# 1-Schematic_CessnaCitationX_AP.net
KiCad netlist of a schematic drawn in EasyEDA
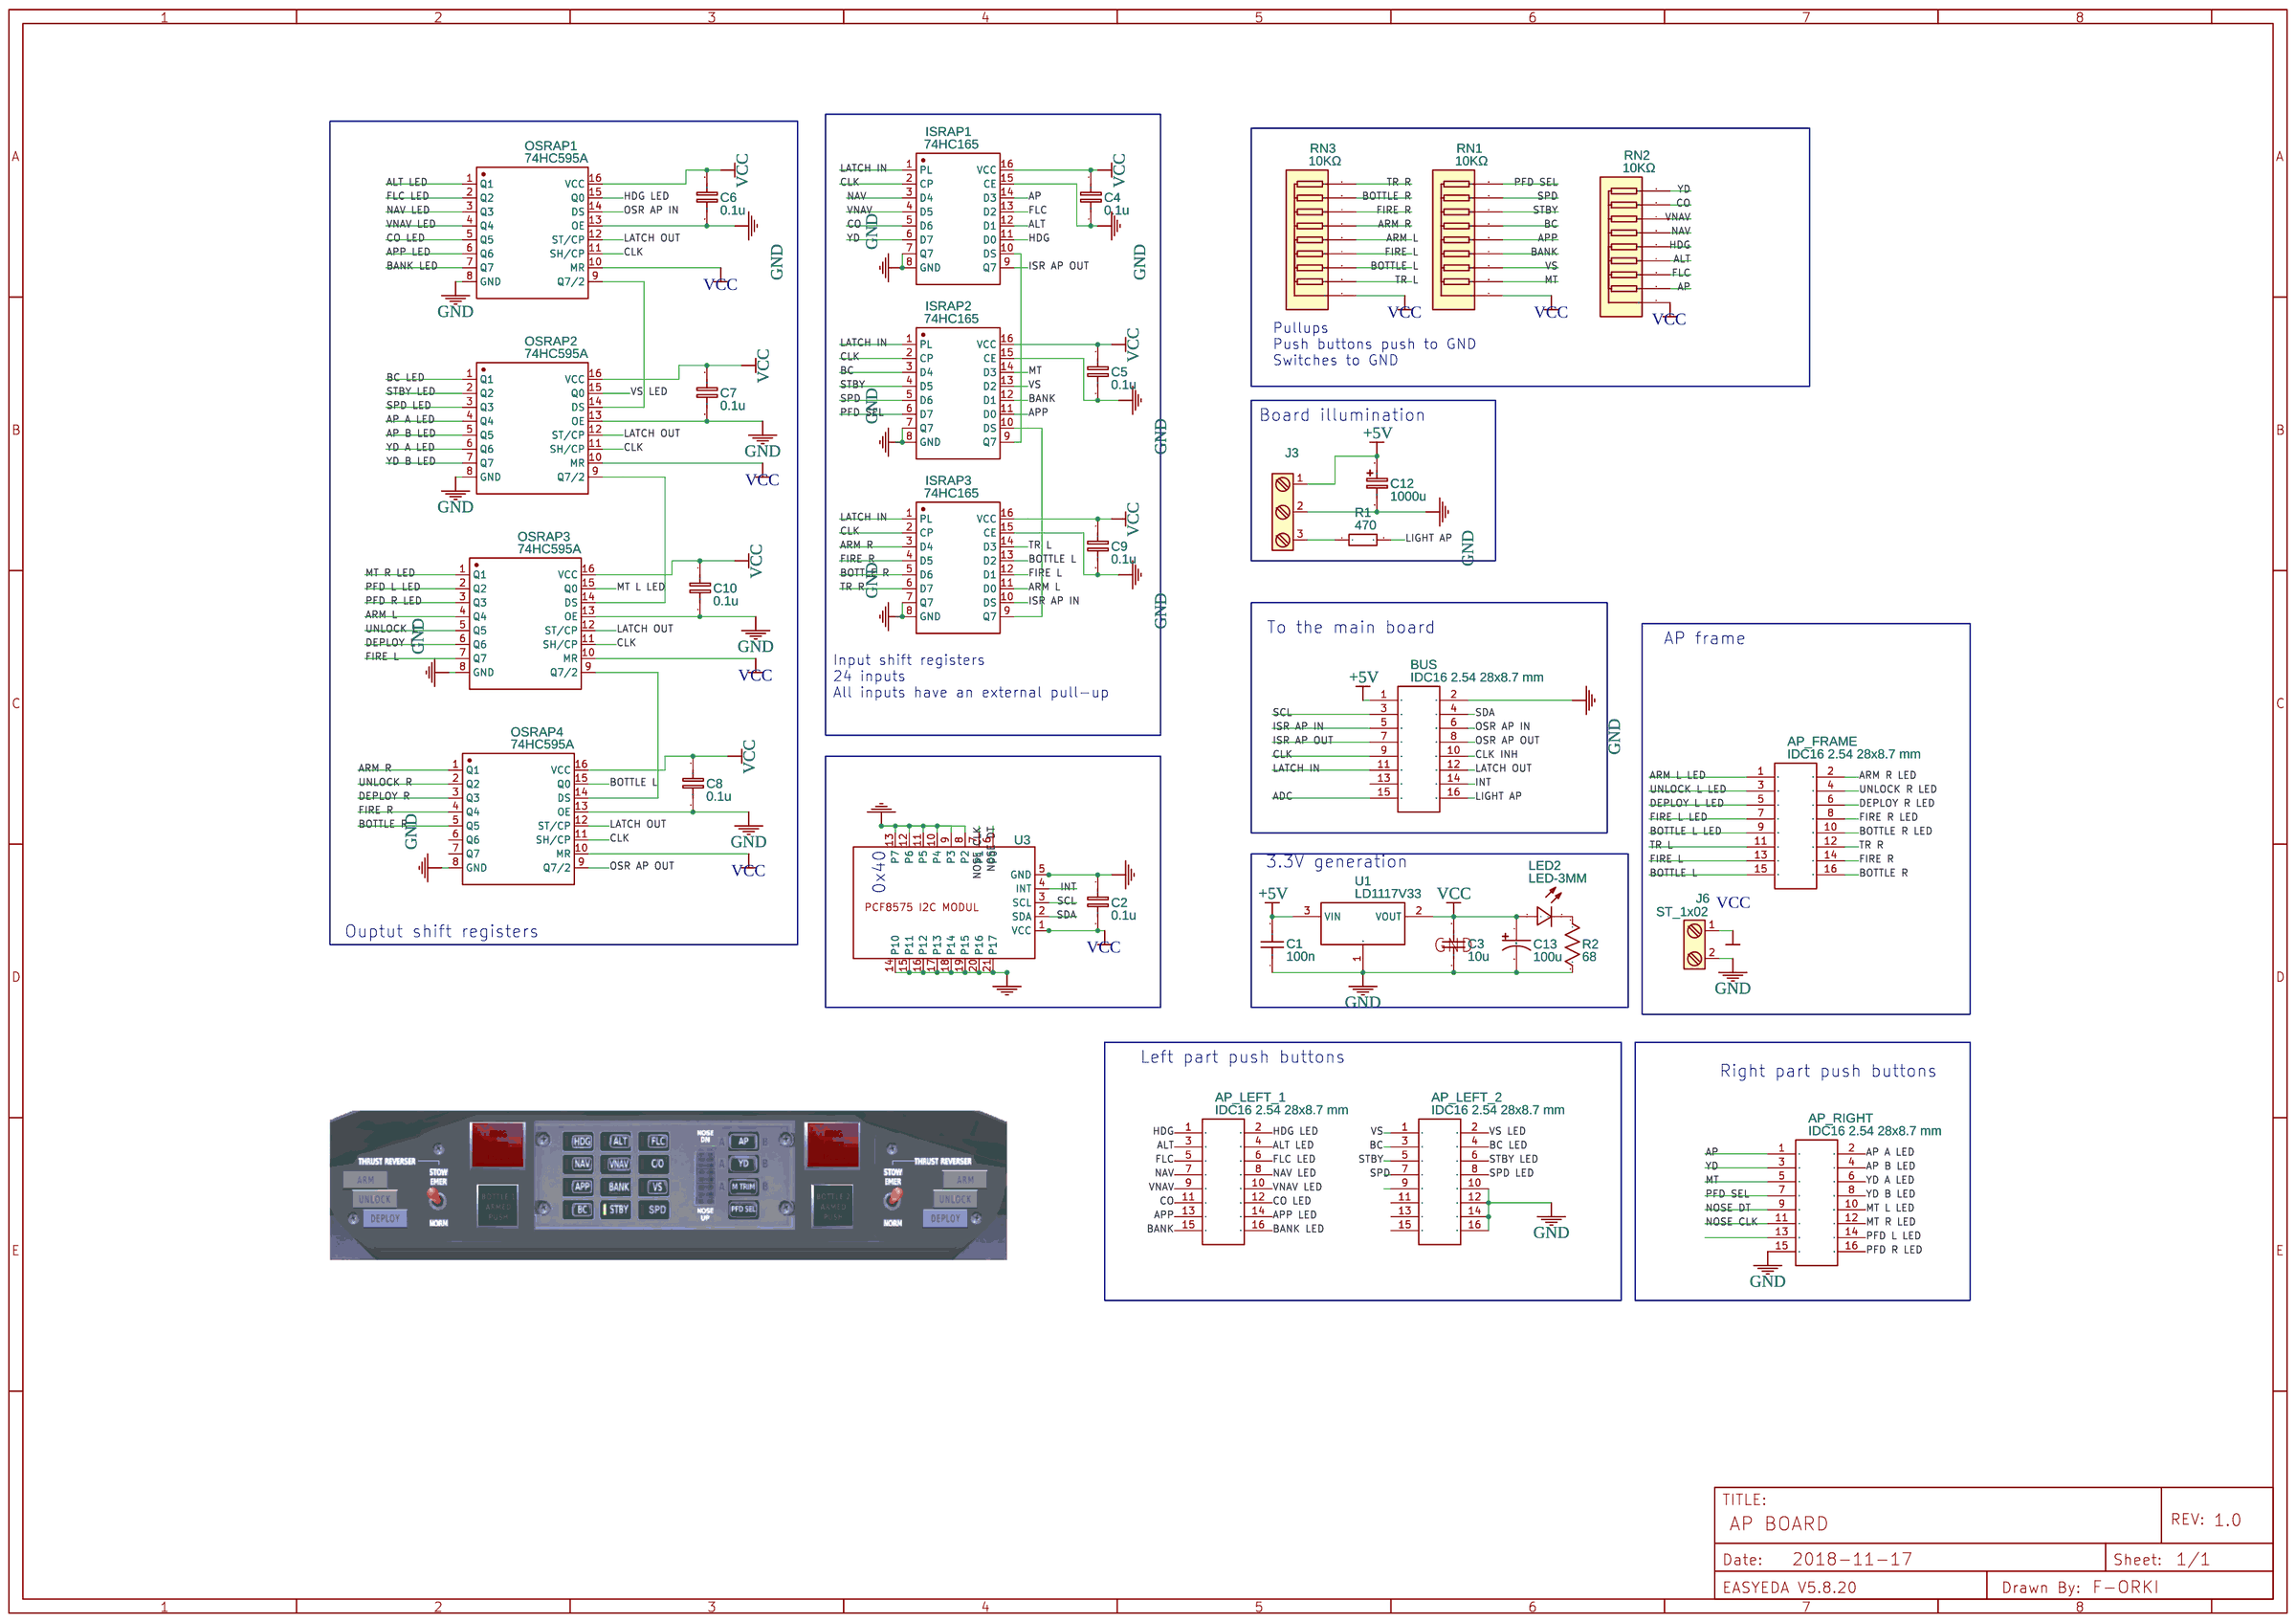
[diagram p0: schematic sheet]

(export (version "E")
  (design (tool "Eeschema 10.0.6"))
  (components
    (comp (ref "AP_FRAME")
      (value "IDC16 2.54 28x8.7 mm")
      (fields (field (name "BOM_Manufacturer Part") "?"))
      (libsource (lib "") (part "Unknown_1245_630"))
    )
    (comp (ref "AP_LEFT_1")
      (value "IDC16 2.54 28x8.7 mm")
      (fields (field (name "BOM_Manufacturer Part") "?"))
      (libsource (lib "") (part "Unknown_835_885"))
    )
    (comp (ref "AP_LEFT_2")
      (value "IDC16 2.54 28x8.7 mm")
      (fields (field (name "BOM_Manufacturer Part") "?"))
      (libsource (lib "") (part "Unknown_990_885"))
    )
    (comp (ref "AP_RIGHT")
      (value "IDC16 2.54 28x8.7 mm")
      (fields (field (name "BOM_Manufacturer Part") "?"))
      (libsource (lib "") (part "Unknown_1260_900"))
    )
    (comp (ref "BUS")
      (value "IDC16 2.54 28x8.7 mm")
      (fields (field (name "BOM_Manufacturer Part") "?"))
      (libsource (lib "") (part "Unknown_975_575"))
    )
    (comp (ref "C1")
      (value "100n")
      (fields (field (name "BOM_Manufacturer Part") "?"))
      (libsource (lib "") (part "Cap_RAD-0.1_US"))
    )
    (comp (ref "C2")
      (value "0.1u")
      (fields (field (name "BOM_Manufacturer Part") "?"))
      (libsource (lib "") (part "Cap_RAD-0.1_EU_1"))
    )
    (comp (ref "C3")
      (value "10u")
      (fields (field (name "BOM_Manufacturer Part") "?"))
      (libsource (lib "") (part "Cap_RAD-0.1_US"))
    )
    (comp (ref "C4")
      (value "0.1u")
      (fields (field (name "BOM_Manufacturer Part") "?"))
      (libsource (lib "") (part "Cap_RAD-0.1_EU"))
    )
    (comp (ref "C5")
      (value "0.1u")
      (fields (field (name "BOM_Manufacturer Part") "?"))
      (libsource (lib "") (part "Cap_RAD-0.1_EU"))
    )
    (comp (ref "C6")
      (value "0.1u")
      (fields (field (name "BOM_Manufacturer Part") "?"))
      (libsource (lib "") (part "Cap_RAD-0.1_EU_2"))
    )
    (comp (ref "C7")
      (value "0.1u")
      (fields (field (name "BOM_Manufacturer Part") "?"))
      (libsource (lib "") (part "Cap_RAD-0.1_EU_2"))
    )
    (comp (ref "C8")
      (value "0.1u")
      (fields (field (name "BOM_Manufacturer Part") "?"))
      (libsource (lib "") (part "Cap_RAD-0.1_EU_3"))
    )
    (comp (ref "C9")
      (value "0.1u")
      (fields (field (name "BOM_Manufacturer Part") "?"))
      (libsource (lib "") (part "Cap_RAD-0.1_EU"))
    )
    (comp (ref "C10")
      (value "0.1u")
      (fields (field (name "BOM_Manufacturer Part") "?"))
      (libsource (lib "") (part "Cap_RAD-0.1_EU_2"))
    )
    (comp (ref "C12")
      (value "1000u")
      (fields (field (name "BOM_Manufacturer Part") "?"))
      (libsource (lib "") (part "Cap_Electrolytic(TH)_D3.0XF1.5_EU"))
    )
    (comp (ref "C13")
      (value "100u")
      (fields (field (name "BOM_Manufacturer Part") "?"))
      (libsource (lib "") (part "Cap_Electrolytic(TH)_D3.0XF1.5_US"))
    )
    (comp (ref "ISRAP1")
      (value "74HC165")
      (fields
        (field (name "BOM_Manufacturer Part") "74HC165D,653")
        (field (name "BOM_Supplier Part") "C5613")
      )
      (libsource (lib "") (part "Unknown_680_105"))
    )
    (comp (ref "ISRAP2")
      (value "74HC165")
      (fields
        (field (name "BOM_Manufacturer Part") "74HC165D,653")
        (field (name "BOM_Supplier Part") "C5613")
      )
      (libsource (lib "") (part "Unknown_680_230"))
    )
    (comp (ref "ISRAP3")
      (value "74HC165")
      (fields
        (field (name "BOM_Manufacturer Part") "74HC165D,653")
        (field (name "BOM_Supplier Part") "C5613")
      )
      (libsource (lib "") (part "Unknown_680_355"))
    )
    (comp (ref "J3")
      (value "Screw_Terminal_1x03")
      (fields (field (name "BOM_Manufacturer Part") "?"))
      (libsource (lib "") (part "Unknown_920_360"))
    )
    (comp (ref "J6")
      (value "ST_1x02")
      (fields (field (name "BOM_Manufacturer Part") "?"))
      (libsource (lib "") (part "Unknown_1215_660"))
    )
    (comp (ref "LED2")
      (value "LED-3MM")
      (fields
        (field (name "BOM_Manufacturer Part") "204-10SURD/S530-A3")
        (field (name "BOM_Supplier Part") "C99772")
      )
      (libsource (lib "") (part "Unknown_1100_645"))
    )
    (comp (ref "OSRAP1")
      (value "74HC595A")
      (fields (field (name "BOM_Supplier Part") "C110383"))
      (libsource (lib "") (part "Unknown_375_115"))
    )
    (comp (ref "OSRAP2")
      (value "74HC595A")
      (fields (field (name "BOM_Supplier Part") "C110383"))
      (libsource (lib "") (part "Unknown_375_255"))
    )
    (comp (ref "OSRAP3")
      (value "74HC595A")
      (fields (field (name "BOM_Supplier Part") "C110383"))
      (libsource (lib "") (part "Unknown_370_395"))
    )
    (comp (ref "OSRAP4")
      (value "74HC595A")
      (fields (field (name "BOM_Supplier Part") "C110383"))
      (libsource (lib "") (part "Unknown_365_535"))
    )
    (comp (ref "R1")
      (value "470")
      (fields (field (name "BOM_Manufacturer Part") "?"))
      (libsource (lib "") (part "Res_AXIAL-0.3(1/8W)_EU"))
    )
    (comp (ref "R2")
      (value "68")
      (fields (field (name "BOM_Manufacturer Part") "?"))
      (libsource (lib "") (part "Res_AXIAL-0.3(1/8W)_US"))
    )
    (comp (ref "RN1")
      (value "10KΩ")
      (fields (field (name "BOM_Manufacturer Part") "A09-103JP") (field (name "BOM_Supplier Part") "C8692"))
      (libsource (lib "") (part "A09-103JP"))
    )
    (comp (ref "RN2")
      (value "10KΩ")
      (fields (field (name "BOM_Manufacturer Part") "A09-103JP") (field (name "BOM_Supplier Part") "C8692"))
      (libsource (lib "") (part "A09-103JP"))
    )
    (comp (ref "RN3")
      (value "10KΩ")
      (fields (field (name "BOM_Manufacturer Part") "A09-103JP") (field (name "BOM_Supplier Part") "C8692"))
      (libsource (lib "") (part "A09-103JP"))
    )
    (comp (ref "U1")
      (value "LD1117V33")
      (fields (field (name "BOM_Supplier Part") "C283467"))
      (libsource (lib "") (part "Unknown_970_670"))
    )
    (comp (ref "U3")
      (value "PCF8575C")
      (fields (field (name "BOM_Manufacturer Part") "?"))
      (libsource (lib "") (part "Unknown_615_700"))
    )
  )
  (nets
    (net (code "1") (name "+5V") (class "Default")
      (node (ref "BUS") (pin "1") (pinfunction "P1_1") (pintype "unspecified"))
      (node (ref "C1") (pin "2") (pinfunction "2_2") (pintype "unspecified"))
      (node (ref "C12") (pin "1") (pinfunction "1_1") (pintype "unspecified"))
      (node (ref "J3") (pin "1") (pintype "unspecified"))
      (node (ref "U1") (pin "3") (pinfunction "VIN_3") (pintype "passive"))
    )
    (net (code "2") (name "/ADC") (class "Default")
      (node (ref "BUS") (pin "15") (pinfunction "15_15") (pintype "unspecified"))
    )
    (net (code "3") (name "/ALT") (class "Default")
      (node (ref "AP_LEFT_1") (pin "3") (pinfunction "P3_3") (pintype "unspecified"))
      (node (ref "ISRAP1") (pin "12") (pinfunction "D1_12") (pintype "unspecified"))
      (node (ref "RN2") (pin "4") (pinfunction "4_4") (pintype "input"))
    )
    (net (code "4") (name "/ALT LED") (class "Default")
      (node (ref "AP_LEFT_1") (pin "4") (pinfunction "P4_4") (pintype "unspecified"))
      (node (ref "OSRAP1") (pin "1") (pinfunction "Q1_1") (pintype "unspecified"))
    )
    (net (code "5") (name "/AP") (class "Default")
      (node (ref "AP_RIGHT") (pin "1") (pinfunction "P1_1") (pintype "unspecified"))
      (node (ref "ISRAP1") (pin "14") (pinfunction "D3_14") (pintype "unspecified"))
      (node (ref "RN2") (pin "2") (pinfunction "2_2") (pintype "input"))
    )
    (net (code "6") (name "/AP A LED") (class "Default")
      (node (ref "AP_RIGHT") (pin "2") (pinfunction "P2_2") (pintype "unspecified"))
      (node (ref "OSRAP2") (pin "4") (pinfunction "Q4_4") (pintype "unspecified"))
    )
    (net (code "7") (name "/AP B LED") (class "Default")
      (node (ref "AP_RIGHT") (pin "4") (pinfunction "P4_4") (pintype "unspecified"))
      (node (ref "OSRAP2") (pin "5") (pinfunction "Q5_5") (pintype "unspecified"))
    )
    (net (code "8") (name "/APP") (class "Default")
      (node (ref "AP_LEFT_1") (pin "13") (pinfunction "13_13") (pintype "unspecified"))
      (node (ref "ISRAP2") (pin "11") (pinfunction "D0_11") (pintype "unspecified"))
      (node (ref "RN1") (pin "5") (pinfunction "5_5") (pintype "input"))
    )
    (net (code "9") (name "/APP LED") (class "Default")
      (node (ref "AP_LEFT_1") (pin "14") (pinfunction "14_14") (pintype "unspecified"))
      (node (ref "OSRAP1") (pin "6") (pinfunction "Q6_6") (pintype "unspecified"))
    )
    (net (code "10") (name "/ARM L") (class "Default")
      (node (ref "ISRAP3") (pin "11") (pinfunction "D0_11") (pintype "unspecified"))
      (node (ref "OSRAP3") (pin "4") (pinfunction "Q4_4") (pintype "unspecified"))
    )
    (net (code "11") (name "/ARM L LED") (class "Default")
      (node (ref "AP_FRAME") (pin "1") (pinfunction "P1_1") (pintype "unspecified"))
    )
    (net (code "12") (name "/ARM R") (class "Default")
      (node (ref "ISRAP3") (pin "3") (pinfunction "D4_3") (pintype "unspecified"))
      (node (ref "OSRAP4") (pin "1") (pinfunction "Q1_1") (pintype "unspecified"))
      (node (ref "RN3") (pin "6") (pinfunction "6_6") (pintype "input"))
    )
    (net (code "13") (name "/ARM R LED") (class "Default")
      (node (ref "AP_FRAME") (pin "2") (pinfunction "P2_2") (pintype "unspecified"))
    )
    (net (code "14") (name "/BANK") (class "Default")
      (node (ref "AP_LEFT_1") (pin "15") (pinfunction "15_15") (pintype "unspecified"))
      (node (ref "ISRAP2") (pin "12") (pinfunction "D1_12") (pintype "unspecified"))
      (node (ref "RN1") (pin "4") (pinfunction "4_4") (pintype "input"))
    )
    (net (code "15") (name "/BANK LED") (class "Default")
      (node (ref "AP_LEFT_1") (pin "16") (pinfunction "16_16") (pintype "unspecified"))
      (node (ref "OSRAP1") (pin "7") (pinfunction "Q7_7") (pintype "unspecified"))
    )
    (net (code "16") (name "/BC") (class "Default")
      (node (ref "AP_LEFT_2") (pin "3") (pinfunction "P3_3") (pintype "unspecified"))
      (node (ref "ISRAP2") (pin "3") (pinfunction "D4_3") (pintype "unspecified"))
      (node (ref "RN1") (pin "6") (pinfunction "6_6") (pintype "input"))
    )
    (net (code "17") (name "/BC LED") (class "Default")
      (node (ref "AP_LEFT_2") (pin "4") (pinfunction "P4_4") (pintype "unspecified"))
      (node (ref "OSRAP2") (pin "1") (pinfunction "Q1_1") (pintype "unspecified"))
    )
    (net (code "18") (name "/BOTTLE L") (class "Default")
      (node (ref "AP_FRAME") (pin "15") (pinfunction "15_15") (pintype "unspecified"))
      (node (ref "ISRAP3") (pin "13") (pinfunction "D2_13") (pintype "unspecified"))
      (node (ref "OSRAP4") (pin "15") (pinfunction "Q0_15") (pintype "unspecified"))
    )
    (net (code "19") (name "/BOTTLE L LED") (class "Default")
      (node (ref "AP_FRAME") (pin "9") (pinfunction "P9_9") (pintype "unspecified"))
    )
    (net (code "20") (name "/BOTTLE R") (class "Default")
      (node (ref "AP_FRAME") (pin "16") (pinfunction "16_16") (pintype "unspecified"))
      (node (ref "ISRAP3") (pin "5") (pinfunction "D6_5") (pintype "unspecified"))
      (node (ref "OSRAP4") (pin "5") (pinfunction "Q5_5") (pintype "unspecified"))
      (node (ref "RN3") (pin "8") (pinfunction "8_8") (pintype "input"))
    )
    (net (code "21") (name "/BOTTLE R LED") (class "Default")
      (node (ref "AP_FRAME") (pin "10") (pinfunction "P10_10") (pintype "unspecified"))
    )
    (net (code "22") (name "/CLK") (class "Default")
      (node (ref "BUS") (pin "9") (pinfunction "P9_9") (pintype "unspecified"))
      (node (ref "ISRAP1") (pin "2") (pinfunction "CP_2") (pintype "unspecified"))
      (node (ref "ISRAP2") (pin "2") (pinfunction "CP_2") (pintype "unspecified"))
      (node (ref "ISRAP3") (pin "2") (pinfunction "CP_2") (pintype "unspecified"))
      (node (ref "OSRAP1") (pin "11") (pinfunction "SH/CP_11") (pintype "unspecified"))
      (node (ref "OSRAP2") (pin "11") (pinfunction "SH/CP_11") (pintype "unspecified"))
      (node (ref "OSRAP3") (pin "11") (pinfunction "SH/CP_11") (pintype "unspecified"))
      (node (ref "OSRAP4") (pin "11") (pinfunction "SH/CP_11") (pintype "unspecified"))
    )
    (net (code "23") (name "/CLK INH") (class "Default")
      (node (ref "BUS") (pin "10") (pinfunction "P10_10") (pintype "unspecified"))
    )
    (net (code "24") (name "/CO") (class "Default")
      (node (ref "AP_LEFT_1") (pin "11") (pinfunction "11_11") (pintype "unspecified"))
      (node (ref "ISRAP1") (pin "5") (pinfunction "D6_5") (pintype "unspecified"))
      (node (ref "RN2") (pin "8") (pinfunction "8_8") (pintype "input"))
    )
    (net (code "25") (name "/CO LED") (class "Default")
      (node (ref "AP_LEFT_1") (pin "12") (pinfunction "12_12") (pintype "unspecified"))
      (node (ref "OSRAP1") (pin "5") (pinfunction "Q5_5") (pintype "unspecified"))
    )
    (net (code "26") (name "/DEPLOY L") (class "Default")
      (node (ref "OSRAP3") (pin "6") (pinfunction "Q6_6") (pintype "unspecified"))
    )
    (net (code "27") (name "/DEPLOY L LED") (class "Default")
      (node (ref "AP_FRAME") (pin "5") (pinfunction "P5_5") (pintype "unspecified"))
    )
    (net (code "28") (name "/DEPLOY R") (class "Default")
      (node (ref "OSRAP4") (pin "3") (pinfunction "Q3_3") (pintype "unspecified"))
    )
    (net (code "29") (name "/DEPLOY R LED") (class "Default")
      (node (ref "AP_FRAME") (pin "6") (pinfunction "P6_6") (pintype "unspecified"))
    )
    (net (code "30") (name "/FIRE L") (class "Default")
      (node (ref "AP_FRAME") (pin "13") (pinfunction "13_13") (pintype "unspecified"))
      (node (ref "ISRAP3") (pin "12") (pinfunction "D1_12") (pintype "unspecified"))
      (node (ref "OSRAP3") (pin "7") (pinfunction "Q7_7") (pintype "unspecified"))
    )
    (net (code "31") (name "/FIRE L LED") (class "Default")
      (node (ref "AP_FRAME") (pin "7") (pinfunction "P7_7") (pintype "unspecified"))
    )
    (net (code "32") (name "/FIRE R") (class "Default")
      (node (ref "AP_FRAME") (pin "14") (pinfunction "14_14") (pintype "unspecified"))
      (node (ref "ISRAP3") (pin "4") (pinfunction "D5_4") (pintype "unspecified"))
      (node (ref "OSRAP4") (pin "4") (pinfunction "Q4_4") (pintype "unspecified"))
      (node (ref "RN3") (pin "7") (pinfunction "7_7") (pintype "input"))
    )
    (net (code "33") (name "/FIRE R LED") (class "Default")
      (node (ref "AP_FRAME") (pin "8") (pinfunction "P8_8") (pintype "unspecified"))
    )
    (net (code "34") (name "/FLC") (class "Default")
      (node (ref "AP_LEFT_1") (pin "5") (pinfunction "P5_5") (pintype "unspecified"))
      (node (ref "ISRAP1") (pin "13") (pinfunction "D2_13") (pintype "unspecified"))
      (node (ref "RN2") (pin "3") (pinfunction "3_3") (pintype "input"))
    )
    (net (code "35") (name "/FLC LED") (class "Default")
      (node (ref "AP_LEFT_1") (pin "6") (pinfunction "P6_6") (pintype "unspecified"))
      (node (ref "OSRAP1") (pin "2") (pinfunction "Q2_2") (pintype "unspecified"))
    )
    (net (code "36") (name "/HDG") (class "Default")
      (node (ref "AP_LEFT_1") (pin "1") (pinfunction "P1_1") (pintype "unspecified"))
      (node (ref "ISRAP1") (pin "11") (pinfunction "D0_11") (pintype "unspecified"))
      (node (ref "RN2") (pin "5") (pinfunction "5_5") (pintype "input"))
    )
    (net (code "37") (name "/HDG LED") (class "Default")
      (node (ref "AP_LEFT_1") (pin "2") (pinfunction "P2_2") (pintype "unspecified"))
      (node (ref "OSRAP1") (pin "15") (pinfunction "Q0_15") (pintype "unspecified"))
    )
    (net (code "38") (name "/INT") (class "Default")
      (node (ref "BUS") (pin "14") (pinfunction "14_14") (pintype "unspecified"))
      (node (ref "U3") (pin "4") (pinfunction "INT_4") (pintype "unspecified"))
    )
    (net (code "39") (name "/ISR AP IN") (class "Default")
      (node (ref "BUS") (pin "5") (pinfunction "P5_5") (pintype "unspecified"))
      (node (ref "ISRAP3") (pin "10") (pinfunction "DS_10") (pintype "unspecified"))
    )
    (net (code "40") (name "/ISR AP OUT") (class "Default")
      (node (ref "BUS") (pin "7") (pinfunction "P7_7") (pintype "unspecified"))
      (node (ref "ISRAP1") (pin "9") (pinfunction "Q7_9") (pintype "unspecified"))
    )
    (net (code "41") (name "/LATCH IN") (class "Default")
      (node (ref "BUS") (pin "11") (pinfunction "11_11") (pintype "unspecified"))
      (node (ref "ISRAP1") (pin "1") (pinfunction "PL_1") (pintype "unspecified"))
      (node (ref "ISRAP2") (pin "1") (pinfunction "PL_1") (pintype "unspecified"))
      (node (ref "ISRAP3") (pin "1") (pinfunction "PL_1") (pintype "unspecified"))
    )
    (net (code "42") (name "/LATCH OUT") (class "Default")
      (node (ref "BUS") (pin "12") (pinfunction "12_12") (pintype "unspecified"))
      (node (ref "OSRAP1") (pin "12") (pinfunction "ST/CP_12") (pintype "unspecified"))
      (node (ref "OSRAP2") (pin "12") (pinfunction "ST/CP_12") (pintype "unspecified"))
      (node (ref "OSRAP3") (pin "12") (pinfunction "ST/CP_12") (pintype "unspecified"))
      (node (ref "OSRAP4") (pin "12") (pinfunction "ST/CP_12") (pintype "unspecified"))
    )
    (net (code "43") (name "/LIGHT AP") (class "Default")
      (node (ref "BUS") (pin "16") (pinfunction "16_16") (pintype "unspecified"))
      (node (ref "R1") (pin "2") (pinfunction "2_2") (pintype "unspecified"))
    )
    (net (code "44") (name "/MT") (class "Default")
      (node (ref "AP_RIGHT") (pin "5") (pinfunction "P5_5") (pintype "unspecified"))
      (node (ref "ISRAP2") (pin "14") (pinfunction "D3_14") (pintype "unspecified"))
      (node (ref "RN1") (pin "2") (pinfunction "2_2") (pintype "input"))
    )
    (net (code "45") (name "/MT L LED") (class "Default")
      (node (ref "AP_RIGHT") (pin "10") (pinfunction "P10_10") (pintype "unspecified"))
      (node (ref "OSRAP3") (pin "15") (pinfunction "Q0_15") (pintype "unspecified"))
    )
    (net (code "46") (name "/MT R LED") (class "Default")
      (node (ref "AP_RIGHT") (pin "12") (pinfunction "12_12") (pintype "unspecified"))
      (node (ref "OSRAP3") (pin "1") (pinfunction "Q1_1") (pintype "unspecified"))
    )
    (net (code "47") (name "/NAV") (class "Default")
      (node (ref "AP_LEFT_1") (pin "7") (pinfunction "P7_7") (pintype "unspecified"))
      (node (ref "ISRAP1") (pin "3") (pinfunction "D4_3") (pintype "unspecified"))
      (node (ref "RN2") (pin "6") (pinfunction "6_6") (pintype "input"))
    )
    (net (code "48") (name "/NAV LED") (class "Default")
      (node (ref "AP_LEFT_1") (pin "8") (pinfunction "P8_8") (pintype "unspecified"))
      (node (ref "OSRAP1") (pin "3") (pinfunction "Q3_3") (pintype "unspecified"))
    )
    (net (code "49") (name "/NOSE CLK") (class "Default")
      (node (ref "AP_RIGHT") (pin "11") (pinfunction "11_11") (pintype "unspecified"))
      (node (ref "U3") (pin "7") (pinfunction "P1_7") (pintype "unspecified"))
    )
    (net (code "50") (name "/NOSE DT") (class "Default")
      (node (ref "AP_RIGHT") (pin "9") (pinfunction "P9_9") (pintype "unspecified"))
      (node (ref "U3") (pin "6") (pinfunction "P0_6") (pintype "unspecified"))
    )
    (net (code "51") (name "/OSR AP IN") (class "Default")
      (node (ref "BUS") (pin "6") (pinfunction "P6_6") (pintype "unspecified"))
      (node (ref "OSRAP1") (pin "14") (pinfunction "DS_14") (pintype "unspecified"))
    )
    (net (code "52") (name "/OSR AP OUT") (class "Default")
      (node (ref "BUS") (pin "8") (pinfunction "P8_8") (pintype "unspecified"))
      (node (ref "OSRAP4") (pin "9") (pinfunction "Q7/2_9") (pintype "unspecified"))
    )
    (net (code "53") (name "/PFD L LED") (class "Default")
      (node (ref "AP_RIGHT") (pin "14") (pinfunction "14_14") (pintype "unspecified"))
      (node (ref "OSRAP3") (pin "2") (pinfunction "Q2_2") (pintype "unspecified"))
    )
    (net (code "54") (name "/PFD R LED") (class "Default")
      (node (ref "AP_RIGHT") (pin "16") (pinfunction "16_16") (pintype "unspecified"))
      (node (ref "OSRAP3") (pin "3") (pinfunction "Q3_3") (pintype "unspecified"))
    )
    (net (code "55") (name "/PFD SEL") (class "Default")
      (node (ref "AP_RIGHT") (pin "7") (pinfunction "P7_7") (pintype "unspecified"))
      (node (ref "ISRAP2") (pin "6") (pinfunction "D7_6") (pintype "unspecified"))
      (node (ref "RN1") (pin "9") (pinfunction "9_9") (pintype "input"))
    )
    (net (code "56") (name "/SCL") (class "Default")
      (node (ref "BUS") (pin "3") (pinfunction "P3_3") (pintype "unspecified"))
      (node (ref "U3") (pin "3") (pinfunction "SCL_3") (pintype "unspecified"))
    )
    (net (code "57") (name "/SDA") (class "Default")
      (node (ref "BUS") (pin "4") (pinfunction "P4_4") (pintype "unspecified"))
      (node (ref "U3") (pin "2") (pinfunction "SDA_2") (pintype "unspecified"))
    )
    (net (code "58") (name "/SPD") (class "Default")
      (node (ref "AP_LEFT_2") (pin "7") (pinfunction "P7_7") (pintype "unspecified"))
      (node (ref "ISRAP2") (pin "5") (pinfunction "D6_5") (pintype "unspecified"))
      (node (ref "RN1") (pin "8") (pinfunction "8_8") (pintype "input"))
    )
    (net (code "59") (name "/SPD LED") (class "Default")
      (node (ref "AP_LEFT_2") (pin "8") (pinfunction "P8_8") (pintype "unspecified"))
      (node (ref "OSRAP2") (pin "3") (pinfunction "Q3_3") (pintype "unspecified"))
    )
    (net (code "60") (name "/STBY") (class "Default")
      (node (ref "AP_LEFT_2") (pin "5") (pinfunction "P5_5") (pintype "unspecified"))
      (node (ref "ISRAP2") (pin "4") (pinfunction "D5_4") (pintype "unspecified"))
      (node (ref "RN1") (pin "7") (pinfunction "7_7") (pintype "input"))
    )
    (net (code "61") (name "/STBY LED") (class "Default")
      (node (ref "AP_LEFT_2") (pin "6") (pinfunction "P6_6") (pintype "unspecified"))
      (node (ref "OSRAP2") (pin "2") (pinfunction "Q2_2") (pintype "unspecified"))
    )
    (net (code "62") (name "/TR L") (class "Default")
      (node (ref "AP_FRAME") (pin "11") (pinfunction "11_11") (pintype "unspecified"))
      (node (ref "ISRAP3") (pin "14") (pinfunction "D3_14") (pintype "unspecified"))
    )
    (net (code "63") (name "/TR R") (class "Default")
      (node (ref "AP_FRAME") (pin "12") (pinfunction "12_12") (pintype "unspecified"))
      (node (ref "ISRAP3") (pin "6") (pinfunction "D7_6") (pintype "unspecified"))
      (node (ref "RN3") (pin "9") (pinfunction "9_9") (pintype "input"))
    )
    (net (code "64") (name "/UNLOCK L") (class "Default")
      (node (ref "OSRAP3") (pin "5") (pinfunction "Q5_5") (pintype "unspecified"))
    )
    (net (code "65") (name "/UNLOCK L LED") (class "Default")
      (node (ref "AP_FRAME") (pin "3") (pinfunction "P3_3") (pintype "unspecified"))
    )
    (net (code "66") (name "/UNLOCK R") (class "Default")
      (node (ref "OSRAP4") (pin "2") (pinfunction "Q2_2") (pintype "unspecified"))
    )
    (net (code "67") (name "/UNLOCK R LED") (class "Default")
      (node (ref "AP_FRAME") (pin "4") (pinfunction "P4_4") (pintype "unspecified"))
    )
    (net (code "68") (name "/VNAV") (class "Default")
      (node (ref "AP_LEFT_1") (pin "9") (pinfunction "P9_9") (pintype "unspecified"))
      (node (ref "ISRAP1") (pin "4") (pinfunction "D5_4") (pintype "unspecified"))
      (node (ref "RN2") (pin "7") (pinfunction "7_7") (pintype "input"))
    )
    (net (code "69") (name "/VNAV LED") (class "Default")
      (node (ref "AP_LEFT_1") (pin "10") (pinfunction "P10_10") (pintype "unspecified"))
      (node (ref "OSRAP1") (pin "4") (pinfunction "Q4_4") (pintype "unspecified"))
    )
    (net (code "70") (name "/VS") (class "Default")
      (node (ref "AP_LEFT_2") (pin "1") (pinfunction "P1_1") (pintype "unspecified"))
      (node (ref "ISRAP2") (pin "13") (pinfunction "D2_13") (pintype "unspecified"))
      (node (ref "RN1") (pin "3") (pinfunction "3_3") (pintype "input"))
    )
    (net (code "71") (name "/VS LED") (class "Default")
      (node (ref "AP_LEFT_2") (pin "2") (pinfunction "P2_2") (pintype "unspecified"))
      (node (ref "OSRAP2") (pin "15") (pinfunction "Q0_15") (pintype "unspecified"))
    )
    (net (code "72") (name "/YD") (class "Default")
      (node (ref "AP_RIGHT") (pin "3") (pinfunction "P3_3") (pintype "unspecified"))
      (node (ref "ISRAP1") (pin "6") (pinfunction "D7_6") (pintype "unspecified"))
      (node (ref "RN2") (pin "9") (pinfunction "9_9") (pintype "input"))
    )
    (net (code "73") (name "/YD A LED") (class "Default")
      (node (ref "AP_RIGHT") (pin "6") (pinfunction "P6_6") (pintype "unspecified"))
      (node (ref "OSRAP2") (pin "6") (pinfunction "Q6_6") (pintype "unspecified"))
    )
    (net (code "74") (name "/YD B LED") (class "Default")
      (node (ref "AP_RIGHT") (pin "8") (pinfunction "P8_8") (pintype "unspecified"))
      (node (ref "OSRAP2") (pin "7") (pinfunction "Q7_7") (pintype "unspecified"))
    )
    (net (code "75") (name "GND") (class "Default")
      (node (ref "AP_LEFT_2") (pin "10") (pinfunction "P10_10") (pintype "unspecified"))
      (node (ref "AP_LEFT_2") (pin "12") (pinfunction "12_12") (pintype "unspecified"))
      (node (ref "AP_LEFT_2") (pin "14") (pinfunction "14_14") (pintype "unspecified"))
      (node (ref "AP_LEFT_2") (pin "16") (pinfunction "16_16") (pintype "unspecified"))
      (node (ref "AP_RIGHT") (pin "15") (pinfunction "15_15") (pintype "unspecified"))
      (node (ref "BUS") (pin "2") (pinfunction "P2_2") (pintype "unspecified"))
      (node (ref "C1") (pin "1") (pinfunction "1_1") (pintype "unspecified"))
      (node (ref "C10") (pin "2") (pinfunction "2_2") (pintype "unspecified"))
      (node (ref "C12") (pin "2") (pinfunction "2_2") (pintype "unspecified"))
      (node (ref "C13") (pin "2") (pinfunction "2_2") (pintype "unspecified"))
      (node (ref "C2") (pin "1") (pinfunction "1_1") (pintype "unspecified"))
      (node (ref "C3") (pin "1") (pinfunction "1_1") (pintype "unspecified"))
      (node (ref "C4") (pin "2") (pinfunction "2_2") (pintype "unspecified"))
      (node (ref "C5") (pin "2") (pinfunction "2_2") (pintype "unspecified"))
      (node (ref "C6") (pin "2") (pinfunction "2_2") (pintype "unspecified"))
      (node (ref "C7") (pin "2") (pinfunction "2_2") (pintype "unspecified"))
      (node (ref "C8") (pin "2") (pinfunction "2_2") (pintype "unspecified"))
      (node (ref "C9") (pin "2") (pinfunction "2_2") (pintype "unspecified"))
      (node (ref "ISRAP1") (pin "15") (pinfunction "CE_15") (pintype "unspecified"))
      (node (ref "ISRAP1") (pin "7") (pinfunction "Q7_7") (pintype "unspecified"))
      (node (ref "ISRAP1") (pin "8") (pinfunction "GND_8") (pintype "unspecified"))
      (node (ref "ISRAP2") (pin "15") (pinfunction "CE_15") (pintype "unspecified"))
      (node (ref "ISRAP2") (pin "7") (pinfunction "Q7_7") (pintype "unspecified"))
      (node (ref "ISRAP2") (pin "8") (pinfunction "GND_8") (pintype "unspecified"))
      (node (ref "ISRAP3") (pin "15") (pinfunction "CE_15") (pintype "unspecified"))
      (node (ref "ISRAP3") (pin "7") (pinfunction "Q7_7") (pintype "unspecified"))
      (node (ref "ISRAP3") (pin "8") (pinfunction "GND_8") (pintype "unspecified"))
      (node (ref "J3") (pin "2") (pintype "unspecified"))
      (node (ref "J6") (pin "2") (pintype "unspecified"))
      (node (ref "OSRAP1") (pin "13") (pinfunction "OE_13") (pintype "unspecified"))
      (node (ref "OSRAP1") (pin "8") (pinfunction "GND_8") (pintype "unspecified"))
      (node (ref "OSRAP2") (pin "13") (pinfunction "OE_13") (pintype "unspecified"))
      (node (ref "OSRAP2") (pin "8") (pinfunction "GND_8") (pintype "unspecified"))
      (node (ref "OSRAP3") (pin "13") (pinfunction "OE_13") (pintype "unspecified"))
      (node (ref "OSRAP3") (pin "8") (pinfunction "GND_8") (pintype "unspecified"))
      (node (ref "OSRAP4") (pin "13") (pinfunction "OE_13") (pintype "unspecified"))
      (node (ref "OSRAP4") (pin "8") (pinfunction "GND_8") (pintype "unspecified"))
      (node (ref "R2") (pin "2") (pinfunction "2_2") (pintype "unspecified"))
      (node (ref "U1") (pin "1") (pinfunction "GND_1") (pintype "unspecified"))
      (node (ref "U3") (pin "10") (pinfunction "P4_10") (pintype "unspecified"))
      (node (ref "U3") (pin "11") (pinfunction "P5_11") (pintype "unspecified"))
      (node (ref "U3") (pin "12") (pinfunction "P6_12") (pintype "unspecified"))
      (node (ref "U3") (pin "13") (pinfunction "P7_13") (pintype "unspecified"))
      (node (ref "U3") (pin "14") (pinfunction "P10_14") (pintype "unspecified"))
      (node (ref "U3") (pin "15") (pinfunction "P11_15") (pintype "unspecified"))
      (node (ref "U3") (pin "16") (pinfunction "P12_16") (pintype "unspecified"))
      (node (ref "U3") (pin "17") (pinfunction "P13_17") (pintype "unspecified"))
      (node (ref "U3") (pin "18") (pinfunction "P14_18") (pintype "unspecified"))
      (node (ref "U3") (pin "19") (pinfunction "P15_19") (pintype "unspecified"))
      (node (ref "U3") (pin "20") (pinfunction "P16_20") (pintype "unspecified"))
      (node (ref "U3") (pin "21") (pinfunction "P17_21") (pintype "unspecified"))
      (node (ref "U3") (pin "5") (pinfunction "GND_5") (pintype "unspecified"))
      (node (ref "U3") (pin "8") (pinfunction "P2_8") (pintype "unspecified"))
      (node (ref "U3") (pin "9") (pinfunction "P3_9") (pintype "unspecified"))
    )
    (net (code "76") (name "Net-(ISRAP1-DS)") (class "Default")
      (node (ref "ISRAP1") (pin "10") (pinfunction "DS_10") (pintype "unspecified"))
      (node (ref "ISRAP2") (pin "9") (pinfunction "Q7_9") (pintype "unspecified"))
    )
    (net (code "77") (name "Net-(ISRAP2-DS)") (class "Default")
      (node (ref "ISRAP2") (pin "10") (pinfunction "DS_10") (pintype "unspecified"))
      (node (ref "ISRAP3") (pin "9") (pinfunction "Q7_9") (pintype "unspecified"))
    )
    (net (code "78") (name "Net-(J3-Pad3)") (class "Default")
      (node (ref "J3") (pin "3") (pintype "unspecified"))
      (node (ref "R1") (pin "1") (pinfunction "1_1") (pintype "unspecified"))
    )
    (net (code "79") (name "Net-(LED2--)") (class "Default")
      (node (ref "LED2") (pin "2") (pinfunction "-_2") (pintype "unspecified"))
      (node (ref "R2") (pin "1") (pinfunction "1_1") (pintype "unspecified"))
    )
    (net (code "80") (name "Net-(OSRAP1-Q7{slash}2)") (class "Default")
      (node (ref "OSRAP1") (pin "9") (pinfunction "Q7/2_9") (pintype "unspecified"))
      (node (ref "OSRAP2") (pin "14") (pinfunction "DS_14") (pintype "unspecified"))
    )
    (net (code "81") (name "Net-(OSRAP2-Q7{slash}2)") (class "Default")
      (node (ref "OSRAP2") (pin "9") (pinfunction "Q7/2_9") (pintype "unspecified"))
      (node (ref "OSRAP3") (pin "14") (pinfunction "DS_14") (pintype "unspecified"))
    )
    (net (code "82") (name "Net-(OSRAP3-Q7{slash}2)") (class "Default")
      (node (ref "OSRAP3") (pin "9") (pinfunction "Q7/2_9") (pintype "unspecified"))
      (node (ref "OSRAP4") (pin "14") (pinfunction "DS_14") (pintype "unspecified"))
    )
    (net (code "83") (name "VCC") (class "Default")
      (node (ref "C10") (pin "1") (pinfunction "1_1") (pintype "unspecified"))
      (node (ref "C13") (pin "1") (pinfunction "1_1") (pintype "unspecified"))
      (node (ref "C2") (pin "2") (pinfunction "2_2") (pintype "unspecified"))
      (node (ref "C3") (pin "2") (pinfunction "2_2") (pintype "unspecified"))
      (node (ref "C4") (pin "1") (pinfunction "1_1") (pintype "unspecified"))
      (node (ref "C5") (pin "1") (pinfunction "1_1") (pintype "unspecified"))
      (node (ref "C6") (pin "1") (pinfunction "1_1") (pintype "unspecified"))
      (node (ref "C7") (pin "1") (pinfunction "1_1") (pintype "unspecified"))
      (node (ref "C8") (pin "1") (pinfunction "1_1") (pintype "unspecified"))
      (node (ref "C9") (pin "1") (pinfunction "1_1") (pintype "unspecified"))
      (node (ref "ISRAP1") (pin "16") (pinfunction "VCC_16") (pintype "unspecified"))
      (node (ref "ISRAP2") (pin "16") (pinfunction "VCC_16") (pintype "unspecified"))
      (node (ref "ISRAP3") (pin "16") (pinfunction "VCC_16") (pintype "unspecified"))
      (node (ref "J6") (pin "1") (pintype "unspecified"))
      (node (ref "LED2") (pin "1") (pinfunction "+_1") (pintype "unspecified"))
      (node (ref "OSRAP1") (pin "10") (pinfunction "MR_10") (pintype "unspecified"))
      (node (ref "OSRAP1") (pin "16") (pinfunction "VCC_16") (pintype "unspecified"))
      (node (ref "OSRAP2") (pin "10") (pinfunction "MR_10") (pintype "unspecified"))
      (node (ref "OSRAP2") (pin "16") (pinfunction "VCC_16") (pintype "unspecified"))
      (node (ref "OSRAP3") (pin "10") (pinfunction "MR_10") (pintype "unspecified"))
      (node (ref "OSRAP3") (pin "16") (pinfunction "VCC_16") (pintype "unspecified"))
      (node (ref "OSRAP4") (pin "10") (pinfunction "MR_10") (pintype "unspecified"))
      (node (ref "OSRAP4") (pin "16") (pinfunction "VCC_16") (pintype "unspecified"))
      (node (ref "RN1") (pin "1") (pinfunction "1_1") (pintype "input"))
      (node (ref "RN2") (pin "1") (pinfunction "1_1") (pintype "input"))
      (node (ref "RN3") (pin "1") (pinfunction "1_1") (pintype "input"))
      (node (ref "U1") (pin "2") (pinfunction "VOUT_2") (pintype "passive"))
      (node (ref "U3") (pin "1") (pinfunction "VCC_1") (pintype "unspecified"))
    )
    (net (code "84") (name "unconnected-(AP_LEFT_2-P9-Pad9)") (class "Default")
      (node (ref "AP_LEFT_2") (pin "9") (pinfunction "P9_9") (pintype "unspecified"))
    )
    (net (code "85") (name "unconnected-(AP_LEFT_2-Pad11)") (class "Default")
      (node (ref "AP_LEFT_2") (pin "11") (pinfunction "11_11") (pintype "unspecified"))
    )
    (net (code "86") (name "unconnected-(AP_LEFT_2-Pad13)") (class "Default")
      (node (ref "AP_LEFT_2") (pin "13") (pinfunction "13_13") (pintype "unspecified"))
    )
    (net (code "87") (name "unconnected-(AP_LEFT_2-Pad15)") (class "Default")
      (node (ref "AP_LEFT_2") (pin "15") (pinfunction "15_15") (pintype "unspecified"))
    )
    (net (code "88") (name "unconnected-(AP_RIGHT-Pad13)") (class "Default")
      (node (ref "AP_RIGHT") (pin "13") (pinfunction "13_13") (pintype "unspecified"))
    )
    (net (code "89") (name "unconnected-(BUS-Pad13)") (class "Default")
      (node (ref "BUS") (pin "13") (pinfunction "13_13") (pintype "unspecified"))
    )
    (net (code "90") (name "unconnected-(OSRAP4-Q6-Pad6)") (class "Default")
      (node (ref "OSRAP4") (pin "6") (pinfunction "Q6_6") (pintype "unspecified"))
    )
    (net (code "91") (name "unconnected-(OSRAP4-Q7-Pad7)") (class "Default")
      (node (ref "OSRAP4") (pin "7") (pinfunction "Q7_7") (pintype "unspecified"))
    )
    (net (code "92") (name "unconnected-(RN3-Pad2)") (class "Default")
      (node (ref "RN3") (pin "2") (pinfunction "2_2") (pintype "input"))
    )
    (net (code "93") (name "unconnected-(RN3-Pad3)") (class "Default")
      (node (ref "RN3") (pin "3") (pinfunction "3_3") (pintype "input"))
    )
    (net (code "94") (name "unconnected-(RN3-Pad4)") (class "Default")
      (node (ref "RN3") (pin "4") (pinfunction "4_4") (pintype "input"))
    )
    (net (code "95") (name "unconnected-(RN3-Pad5)") (class "Default")
      (node (ref "RN3") (pin "5") (pinfunction "5_5") (pintype "input"))
    )
  )
)
